# 5V_regulator_V2.net
KiCad netlist of a schematic drawn in Altium Designer
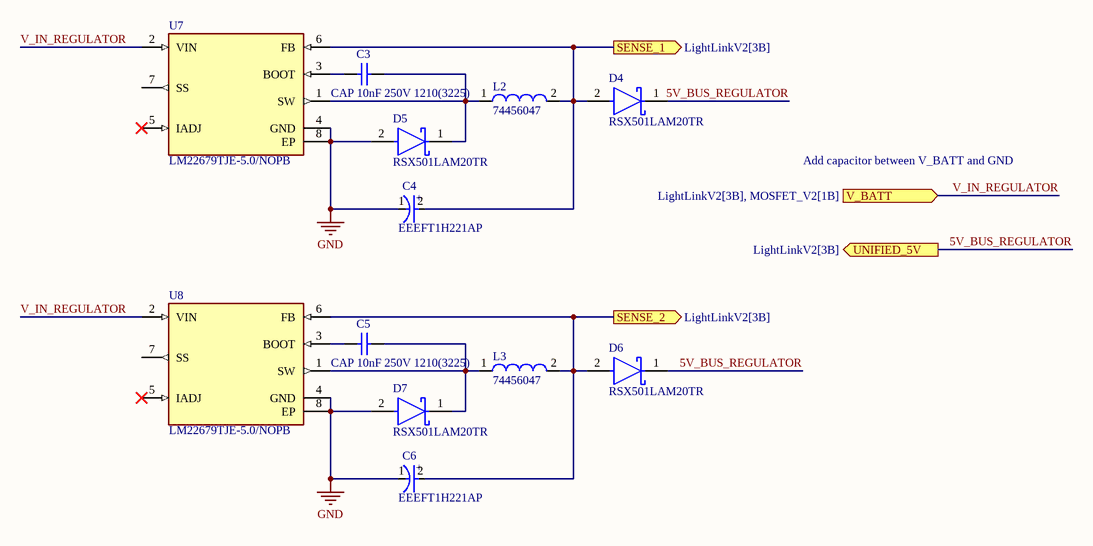
[diagram p0: 5V_regulator_V2.SchDoc]

(export (version "E")
  (design (tool "Eeschema 10.0.6"))
  (components
    (comp (ref "C3")
      (value "CAP 10nF 250V 1210(3225)")
      (footprint "CAPC1210(3225)100_N")
      (description "CAP 10nF 250V ±10% 1210 (3225 Metric) Thickness 1mm SMD")
      (fields (field (name "TOLERANCE") "Â±10%"))
      (libsource (lib "Altium Content Vault") (part "CAP"))
    )
    (comp (ref "C4")
      (value "EEEFT1H221AP")
      (footprint "FP-FTF-MFG")
      (description "CAP ALUM 220UF 20% 50V SMD")
      (fields (field (name "TOLERANCE") "20%") (field (name "VOLTAGE") "50V"))
      (libsource (lib "Altium Content Vault") (part "203bc49f2ac43e59fd269a8c329ed05"))
    )
    (comp (ref "C5")
      (value "CAP 10nF 250V 1210(3225)")
      (footprint "CAPC1210(3225)100_N")
      (description "CAP 10nF 250V ±10% 1210 (3225 Metric) Thickness 1mm SMD")
      (fields (field (name "TOLERANCE") "Â±10%"))
      (libsource (lib "Altium Content Vault") (part "CAP"))
    )
    (comp (ref "C6")
      (value "EEEFT1H221AP")
      (footprint "FP-FTF-MFG")
      (description "CAP ALUM 220UF 20% 50V SMD")
      (fields (field (name "TOLERANCE") "20%") (field (name "VOLTAGE") "50V"))
      (libsource (lib "Altium Content Vault") (part "203bc49f2ac43e59fd269a8c329ed05"))
    )
    (comp (ref "D4")
      (value "RSX501LAM20TR")
      (footprint "FP-PMDTM-MFG")
      (description "DIODE SCHOTTKY 20V 5A PMDTM")
      (fields
        (field (name "OCTOPART") "https://octopart.com/rsx501lam20tr-rohm-82270774")
        (field (name "MANUFACTURER") "Rohm")
      )
      (libsource (lib "Altium Content Vault") (part "1d6ec82d83fb6aee721767c19dac4b9"))
    )
    (comp (ref "D5")
      (value "RSX501LAM20TR")
      (footprint "FP-PMDTM-MFG")
      (description "DIODE SCHOTTKY 20V 5A PMDTM")
      (fields
        (field (name "OCTOPART") "https://octopart.com/rsx501lam20tr-rohm-82270774")
        (field (name "MANUFACTURER") "Rohm")
      )
      (libsource (lib "Altium Content Vault") (part "1d6ec82d83fb6aee721767c19dac4b9"))
    )
    (comp (ref "D6")
      (value "RSX501LAM20TR")
      (footprint "FP-PMDTM-MFG")
      (description "DIODE SCHOTTKY 20V 5A PMDTM")
      (fields
        (field (name "OCTOPART") "https://octopart.com/rsx501lam20tr-rohm-82270774")
        (field (name "MANUFACTURER") "Rohm")
      )
      (libsource (lib "Altium Content Vault") (part "1d6ec82d83fb6aee721767c19dac4b9"))
    )
    (comp (ref "D7")
      (value "RSX501LAM20TR")
      (footprint "FP-PMDTM-MFG")
      (description "DIODE SCHOTTKY 20V 5A PMDTM")
      (fields
        (field (name "OCTOPART") "https://octopart.com/rsx501lam20tr-rohm-82270774")
        (field (name "MANUFACTURER") "Rohm")
      )
      (libsource (lib "Altium Content Vault") (part "1d6ec82d83fb6aee721767c19dac4b9"))
    )
    (comp (ref "L2")
      (value "74456047")
      (footprint "WE-PD4-L")
      (description "SMD-Power Inductor WE-PD4, L = 4.70 µH")
      (libsource (lib "Altium Content Vault") (part "PAS-IND-INDUCTOR-2"))
    )
    (comp (ref "L3")
      (value "74456047")
      (footprint "WE-PD4-L")
      (description "SMD-Power Inductor WE-PD4, L = 4.70 µH")
      (libsource (lib "Altium Content Vault") (part "PAS-IND-INDUCTOR-2"))
    )
    (comp (ref "U7")
      (value "LM22679TJE-5.0/NOPB")
      (footprint "FP-NDR0007A-MFG")
      (description "IC REG BUCK 5V 5A TO263-7")
      (libsource (lib "Altium Content Vault") (part "c21450142ccd96c7b57f3f830d334d0"))
    )
    (comp (ref "U8")
      (value "LM22679TJE-5.0/NOPB")
      (footprint "FP-NDR0007A-MFG")
      (description "IC REG BUCK 5V 5A TO263-7")
      (libsource (lib "Altium Content Vault") (part "c21450142ccd96c7b57f3f830d334d0"))
    )
  )
  (nets
    (net (code "1") (name "/5V_BUS_REGULATOR") (class "Default")
      (node (ref "D4") (pin "1") (pinfunction "C_1") (pintype "passive"))
      (node (ref "D6") (pin "1") (pinfunction "C_1") (pintype "passive"))
    )
    (net (code "2") (name "/SENSE_1") (class "Default")
      (node (ref "C4") (pin "2") (pinfunction "A_2") (pintype "passive"))
      (node (ref "D4") (pin "2") (pinfunction "A_2") (pintype "passive"))
      (node (ref "L2") (pin "2") (pinfunction "2_2") (pintype "passive"))
      (node (ref "U7") (pin "6") (pinfunction "FB_6") (pintype "input"))
    )
    (net (code "3") (name "/SENSE_2") (class "Default")
      (node (ref "C6") (pin "2") (pinfunction "A_2") (pintype "passive"))
      (node (ref "D6") (pin "2") (pinfunction "A_2") (pintype "passive"))
      (node (ref "L3") (pin "2") (pinfunction "2_2") (pintype "passive"))
      (node (ref "U8") (pin "6") (pinfunction "FB_6") (pintype "input"))
    )
    (net (code "4") (name "/V_IN_REGULATOR") (class "Default")
      (node (ref "U7") (pin "2") (pinfunction "VIN_2") (pintype "input"))
      (node (ref "U8") (pin "2") (pinfunction "VIN_2") (pintype "input"))
    )
    (net (code "5") (name "GND") (class "Default")
      (node (ref "C4") (pin "1") (pinfunction "C_1") (pintype "passive"))
      (node (ref "C6") (pin "1") (pinfunction "C_1") (pintype "passive"))
      (node (ref "D5") (pin "2") (pinfunction "A_2") (pintype "passive"))
      (node (ref "D7") (pin "2") (pinfunction "A_2") (pintype "passive"))
      (node (ref "U7") (pin "4") (pinfunction "GND_4") (pintype "power_in"))
      (node (ref "U7") (pin "8") (pinfunction "EP_8") (pintype "power_in"))
      (node (ref "U8") (pin "4") (pinfunction "GND_4") (pintype "power_in"))
      (node (ref "U8") (pin "8") (pinfunction "EP_8") (pintype "power_in"))
    )
    (net (code "6") (name "Net-(D5-C)") (class "Default")
      (node (ref "C3") (pin "2") (pinfunction "2_2") (pintype "passive"))
      (node (ref "D5") (pin "1") (pinfunction "C_1") (pintype "passive"))
      (node (ref "L2") (pin "1") (pinfunction "1_1") (pintype "passive"))
      (node (ref "U7") (pin "1") (pinfunction "SW_1") (pintype "output"))
    )
    (net (code "7") (name "Net-(D7-C)") (class "Default")
      (node (ref "C5") (pin "2") (pinfunction "2_2") (pintype "passive"))
      (node (ref "D7") (pin "1") (pinfunction "C_1") (pintype "passive"))
      (node (ref "L3") (pin "1") (pinfunction "1_1") (pintype "passive"))
      (node (ref "U8") (pin "1") (pinfunction "SW_1") (pintype "output"))
    )
    (net (code "8") (name "Net-(U7-BOOT)") (class "Default")
      (node (ref "C3") (pin "1") (pinfunction "1_1") (pintype "passive"))
      (node (ref "U7") (pin "3") (pinfunction "BOOT_3") (pintype "input"))
    )
    (net (code "9") (name "Net-(U8-BOOT)") (class "Default")
      (node (ref "C5") (pin "1") (pinfunction "1_1") (pintype "passive"))
      (node (ref "U8") (pin "3") (pinfunction "BOOT_3") (pintype "input"))
    )
    (net (code "10") (name "unconnected-(U7-IADJ-Pad5)") (class "Default")
      (node (ref "U7") (pin "5") (pinfunction "IADJ_5") (pintype "input+no_connect"))
    )
    (net (code "11") (name "unconnected-(U7-SS-Pad7)") (class "Default")
      (node (ref "U7") (pin "7") (pinfunction "SS_7") (pintype "output"))
    )
    (net (code "12") (name "unconnected-(U8-IADJ-Pad5)") (class "Default")
      (node (ref "U8") (pin "5") (pinfunction "IADJ_5") (pintype "input+no_connect"))
    )
    (net (code "13") (name "unconnected-(U8-SS-Pad7)") (class "Default")
      (node (ref "U8") (pin "7") (pinfunction "SS_7") (pintype "output"))
    )
  )
)
